# fonte_sim_trica.net
KiCad netlist of a schematic drawn in EAGLE
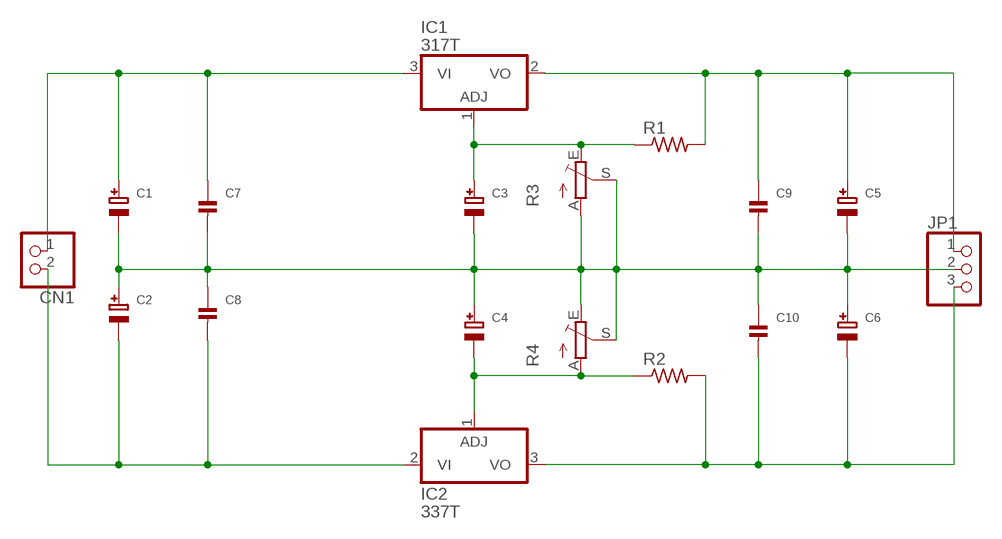
[diagram p0: schematic, sheet 1]

(export (version "E")
  (design (tool "Eeschema 10.0.6"))
  (components
    (comp (ref "C1")
      (value "CAP_ELECTROLYTICPTH_3.5MMGRID_10MMDIA")
      (footprint "eagle-import:CELEC_3.5MM_10MM")
      (libsource (lib "eagle-import") (part "CAP_ELECTROLYTICPTH_3.5MMGRID_10MMDIA"))
    )
    (comp (ref "C2")
      (value "CAP_ELECTROLYTICPTH_3.5MMGRID_10MMDIA")
      (footprint "eagle-import:CELEC_3.5MM_10MM")
      (libsource (lib "eagle-import") (part "CAP_ELECTROLYTICPTH_3.5MMGRID_10MMDIA"))
    )
    (comp (ref "C3")
      (value "CAP_ELECTROLYTICPTH_3.5MMGRID_8MMDIA")
      (footprint "eagle-import:CELEC_3.5MM_8MM")
      (libsource (lib "eagle-import") (part "CAP_ELECTROLYTICPTH_3.5MMGRID_8MMDIA"))
    )
    (comp (ref "C4")
      (value "CAP_ELECTROLYTICPTH_3.5MMGRID_8MMDIA")
      (footprint "eagle-import:CELEC_3.5MM_8MM")
      (libsource (lib "eagle-import") (part "CAP_ELECTROLYTICPTH_3.5MMGRID_8MMDIA"))
    )
    (comp (ref "C5")
      (value "CAP_ELECTROLYTICPTH_3.5MMGRID_8MMDIA")
      (footprint "eagle-import:CELEC_3.5MM_8MM")
      (libsource (lib "eagle-import") (part "CAP_ELECTROLYTICPTH_3.5MMGRID_8MMDIA"))
    )
    (comp (ref "C6")
      (value "CAP_ELECTROLYTICPTH_3.5MMGRID_8MMDIA")
      (footprint "eagle-import:CELEC_3.5MM_8MM")
      (libsource (lib "eagle-import") (part "CAP_ELECTROLYTICPTH_3.5MMGRID_8MMDIA"))
    )
    (comp (ref "C7")
      (value "CAP_CERAMIC0402")
      (footprint "eagle-import:0402")
      (libsource (lib "eagle-import") (part "CAP_CERAMIC0402"))
    )
    (comp (ref "C8")
      (value "CAP_CERAMIC0402")
      (footprint "eagle-import:0402")
      (libsource (lib "eagle-import") (part "CAP_CERAMIC0402"))
    )
    (comp (ref "C9")
      (value "CAP_CERAMIC0402")
      (footprint "eagle-import:0402")
      (libsource (lib "eagle-import") (part "CAP_CERAMIC0402"))
    )
    (comp (ref "C10")
      (value "CAP_CERAMIC0402")
      (footprint "eagle-import:0402")
      (libsource (lib "eagle-import") (part "CAP_CERAMIC0402"))
    )
    (comp (ref "CN1")
      (value "JST_2PIN-SMT")
      (footprint "eagle-import:JST-PH-2-SMT")
      (libsource (lib "eagle-import") (part "JST_2PIN-SMT"))
    )
    (comp (ref "IC1")
      (value "317T")
      (footprint "eagle-import:TO220H")
      (libsource (lib "eagle-import") (part "317T"))
    )
    (comp (ref "IC2")
      (value "337T")
      (footprint "eagle-import:TO220H")
      (libsource (lib "eagle-import") (part "337T"))
    )
    (comp (ref "JP1")
      (value "PINHD-1X3")
      (footprint "eagle-import:1X03")
      (libsource (lib "eagle-import") (part "PINHD-1X3"))
    )
    (comp (ref "R1")
      (value "R-US_0204/7")
      (footprint "eagle-import:0204_7")
      (libsource (lib "eagle-import") (part "R-US_0204/7"))
    )
    (comp (ref "R2")
      (value "R-US_0204/7")
      (footprint "eagle-import:0204_7")
      (libsource (lib "eagle-import") (part "R-US_0204/7"))
    )
    (comp (ref "R3")
      (value "TRIM_1234-S64YW")
      (footprint "eagle-import:S64YW")
      (libsource (lib "eagle-import") (part "TRIM_1234-S64YW"))
    )
    (comp (ref "R4")
      (value "TRIM_1234-S64YW")
      (footprint "eagle-import:S64YW")
      (libsource (lib "eagle-import") (part "TRIM_1234-S64YW"))
    )
  )
  (nets
    (net (code "1") (name "Net-(C7-P$1)") (class "Default")
      (node (ref "C1") (pin "+") (pinfunction "+_+") (pintype "passive"))
      (node (ref "C7") (pin "1") (pinfunction "P$1_1") (pintype "passive"))
      (node (ref "CN1") (pin "1") (pinfunction "2_1") (pintype "passive"))
      (node (ref "IC1") (pin "3") (pinfunction "VI_3") (pintype "input"))
    )
    (net (code "2") (name "Net-(C8-P$2)") (class "Default")
      (node (ref "C2") (pin "-") (pinfunction "-_-") (pintype "passive"))
      (node (ref "C8") (pin "2") (pinfunction "P$2_2") (pintype "passive"))
      (node (ref "CN1") (pin "2") (pinfunction "1_2") (pintype "passive"))
      (node (ref "IC2") (pin "2") (pinfunction "VI_2") (pintype "input"))
    )
    (net (code "3") (name "Net-(C9-P$1)") (class "Default")
      (node (ref "C5") (pin "+") (pinfunction "+_+") (pintype "passive"))
      (node (ref "C9") (pin "1") (pinfunction "P$1_1") (pintype "passive"))
      (node (ref "IC1") (pin "2") (pinfunction "VO_2") (pintype "passive"))
      (node (ref "JP1") (pin "1") (pinfunction "1_1") (pintype "passive"))
      (node (ref "R1") (pin "2") (pinfunction "2_2") (pintype "passive"))
    )
    (net (code "4") (name "Net-(C10-P$1)") (class "Default")
      (node (ref "C1") (pin "-") (pinfunction "-_-") (pintype "passive"))
      (node (ref "C10") (pin "1") (pinfunction "P$1_1") (pintype "passive"))
      (node (ref "C2") (pin "+") (pinfunction "+_+") (pintype "passive"))
      (node (ref "C3") (pin "-") (pinfunction "-_-") (pintype "passive"))
      (node (ref "C4") (pin "+") (pinfunction "+_+") (pintype "passive"))
      (node (ref "C5") (pin "-") (pinfunction "-_-") (pintype "passive"))
      (node (ref "C6") (pin "+") (pinfunction "+_+") (pintype "passive"))
      (node (ref "C7") (pin "2") (pinfunction "P$2_2") (pintype "passive"))
      (node (ref "C8") (pin "1") (pinfunction "P$1_1") (pintype "passive"))
      (node (ref "C9") (pin "2") (pinfunction "P$2_2") (pintype "passive"))
      (node (ref "JP1") (pin "2") (pinfunction "2_2") (pintype "passive"))
      (node (ref "R3") (pin "A") (pinfunction "A_A") (pintype "passive"))
      (node (ref "R3") (pin "S") (pinfunction "S_S") (pintype "passive"))
      (node (ref "R4") (pin "E") (pinfunction "E_E") (pintype "passive"))
      (node (ref "R4") (pin "S") (pinfunction "S_S") (pintype "passive"))
    )
    (net (code "5") (name "Net-(C10-P$2)") (class "Default")
      (node (ref "C10") (pin "2") (pinfunction "P$2_2") (pintype "passive"))
      (node (ref "C6") (pin "-") (pinfunction "-_-") (pintype "passive"))
      (node (ref "IC2") (pin "3") (pinfunction "VO_3") (pintype "passive"))
      (node (ref "JP1") (pin "3") (pinfunction "3_3") (pintype "passive"))
      (node (ref "R2") (pin "2") (pinfunction "2_2") (pintype "passive"))
    )
    (net (code "6") (name "Net-(IC1-ADJ)") (class "Default")
      (node (ref "C3") (pin "+") (pinfunction "+_+") (pintype "passive"))
      (node (ref "IC1") (pin "1") (pinfunction "ADJ_1") (pintype "input"))
      (node (ref "R1") (pin "1") (pinfunction "1_1") (pintype "passive"))
      (node (ref "R3") (pin "E") (pinfunction "E_E") (pintype "passive"))
    )
    (net (code "7") (name "Net-(IC2-ADJ)") (class "Default")
      (node (ref "C4") (pin "-") (pinfunction "-_-") (pintype "passive"))
      (node (ref "IC2") (pin "1") (pinfunction "ADJ_1") (pintype "input"))
      (node (ref "R2") (pin "1") (pinfunction "1_1") (pintype "passive"))
      (node (ref "R4") (pin "A") (pinfunction "A_A") (pintype "passive"))
    )
    (net (code "8") (name "unconnected-(R3-S-PadS@1)") (class "Default")
      (node (ref "R3") (pin "S@1") (pinfunction "S_S@1") (pintype "passive"))
    )
    (net (code "9") (name "unconnected-(R4-S-PadS@1)") (class "Default")
      (node (ref "R4") (pin "S@1") (pinfunction "S_S@1") (pintype "passive"))
    )
  )
)
